# mainboard.net
KiCad netlist of a schematic drawn in EAGLE
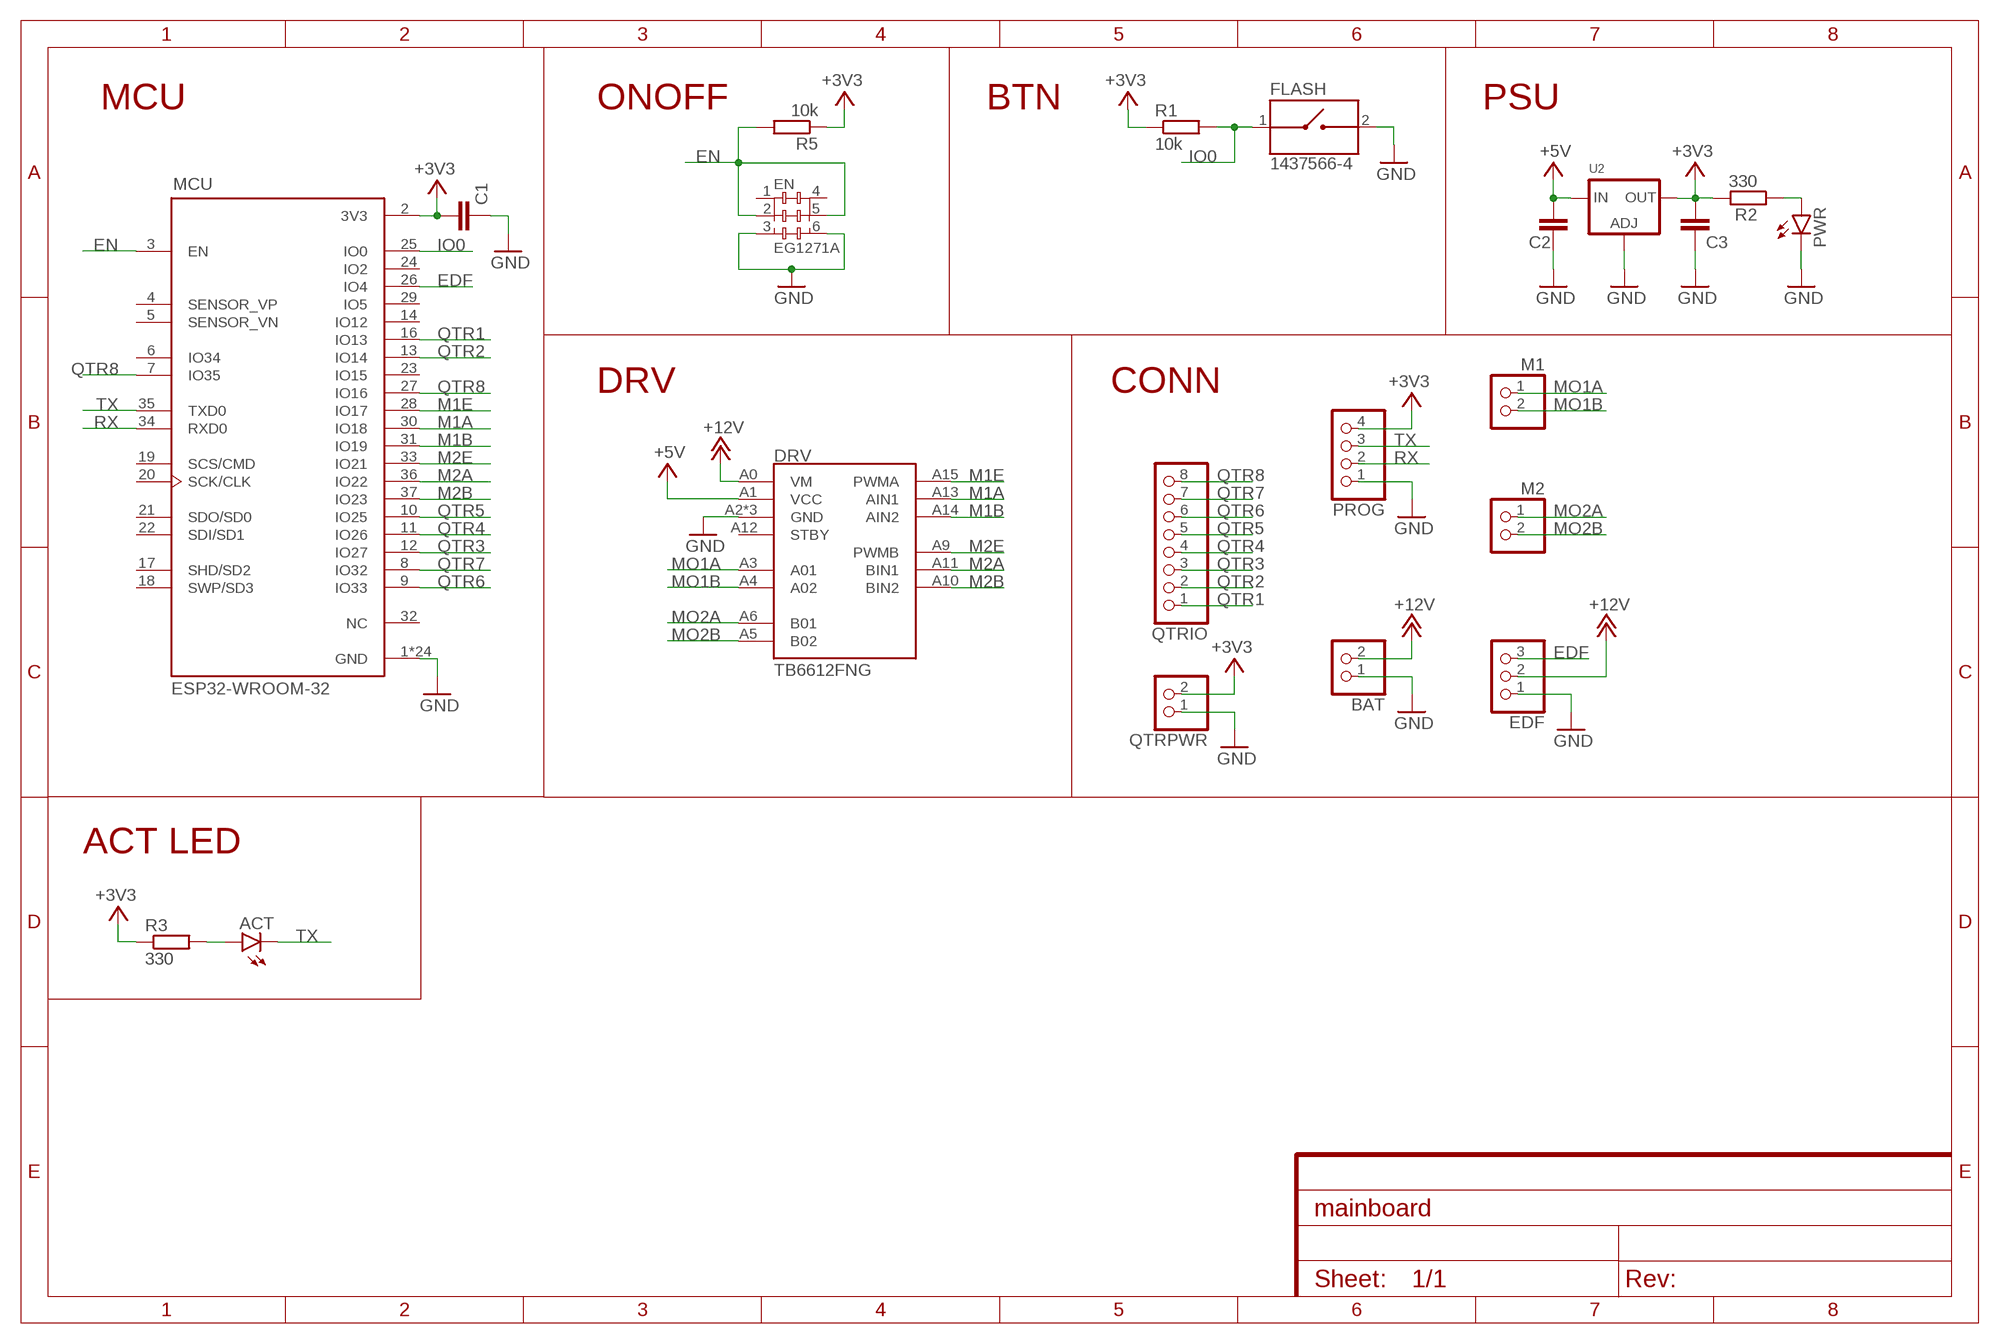
[diagram p0: schematic, sheet 1]

(export (version "E")
  (design (tool "Eeschema 10.0.6"))
  (components
    (comp (ref "ACT")
      (value "LEDCHIPLED_0805")
      (footprint "eagle-import:CHIPLED_0805")
      (libsource (lib "eagle-import") (part "LEDCHIPLED_0805"))
    )
    (comp (ref "BAT")
      (value "PINHD-1X2")
      (footprint "eagle-import:1X02")
      (libsource (lib "eagle-import") (part "PINHD-1X2"))
    )
    (comp (ref "C1")
      (value "C-EUC0805")
      (footprint "eagle-import:C0805")
      (libsource (lib "eagle-import") (part "C-EUC0805"))
    )
    (comp (ref "C2")
      (value "C-EUC0805")
      (footprint "eagle-import:C0805")
      (libsource (lib "eagle-import") (part "C-EUC0805"))
    )
    (comp (ref "C3")
      (value "C-EUC0805")
      (footprint "eagle-import:C0805")
      (libsource (lib "eagle-import") (part "C-EUC0805"))
    )
    (comp (ref "DRV")
      (value "TB6612FNG")
      (footprint "eagle-import:TB6612FNG")
      (libsource (lib "eagle-import") (part "TB6612FNG"))
    )
    (comp (ref "EDF")
      (value "PINHD-1X3")
      (footprint "eagle-import:1X03")
      (libsource (lib "eagle-import") (part "PINHD-1X3"))
    )
    (comp (ref "EN")
      (value "EG1271A")
      (footprint "eagle-import:SW_EG1271A")
      (fields (field (name "MF") "E-Switch"))
      (libsource (lib "eagle-import") (part "EG1271A"))
    )
    (comp (ref "FLASH")
      (value "1437566-4")
      (footprint "eagle-import:SW_1437566-4")
      (fields (field (name "MF") "TE Connectivity"))
      (libsource (lib "eagle-import") (part "1437566-4"))
    )
    (comp (ref "M1")
      (value "PINHD-1X2")
      (footprint "eagle-import:1X02")
      (libsource (lib "eagle-import") (part "PINHD-1X2"))
    )
    (comp (ref "M2")
      (value "PINHD-1X2")
      (footprint "eagle-import:1X02")
      (libsource (lib "eagle-import") (part "PINHD-1X2"))
    )
    (comp (ref "MCU")
      (value "ESP32-WROOM-32")
      (footprint "eagle-import:MODULE_ESP32-WROOM-32")
      (fields (field (name "MF") "Espressif Systems"))
      (libsource (lib "eagle-import") (part "ESP32-WROOM-32"))
    )
    (comp (ref "PROG")
      (value "PINHD-1X4")
      (footprint "eagle-import:1X04")
      (libsource (lib "eagle-import") (part "PINHD-1X4"))
    )
    (comp (ref "PWR")
      (value "LEDCHIPLED_0805")
      (footprint "eagle-import:CHIPLED_0805")
      (libsource (lib "eagle-import") (part "LEDCHIPLED_0805"))
    )
    (comp (ref "QTRIO")
      (value "PINHD-1X8")
      (footprint "eagle-import:1X08")
      (libsource (lib "eagle-import") (part "PINHD-1X8"))
    )
    (comp (ref "QTRPWR")
      (value "PINHD-1X2")
      (footprint "eagle-import:1X02")
      (libsource (lib "eagle-import") (part "PINHD-1X2"))
    )
    (comp (ref "R1")
      (value "10k")
      (footprint "eagle-import:R0603")
      (libsource (lib "eagle-import") (part "R-EU_R0603"))
    )
    (comp (ref "R2")
      (value "330")
      (footprint "eagle-import:R0603")
      (libsource (lib "eagle-import") (part "R-EU_R0603"))
    )
    (comp (ref "R3")
      (value "330")
      (footprint "eagle-import:R0603")
      (libsource (lib "eagle-import") (part "R-EU_R0603"))
    )
    (comp (ref "R5")
      (value "10k")
      (footprint "eagle-import:R0603")
      (libsource (lib "eagle-import") (part "R-EU_R0603"))
    )
    (comp (ref "U2")
      (value "LM1117SOT223-WAVE")
      (footprint "eagle-import:SOT223-W")
      (libsource (lib "eagle-import") (part "LM1117SOT223-WAVE"))
    )
  )
  (nets
    (net (code "1") (name "+3V3") (class "Default")
      (node (ref "C1") (pin "1") (pinfunction "1_1") (pintype "passive"))
      (node (ref "C3") (pin "1") (pinfunction "1_1") (pintype "passive"))
      (node (ref "MCU") (pin "2") (pinfunction "3V3_2") (pintype "power_in"))
      (node (ref "PROG") (pin "4") (pinfunction "4_4") (pintype "passive"))
      (node (ref "QTRPWR") (pin "2") (pinfunction "2_2") (pintype "passive"))
      (node (ref "R1") (pin "1") (pinfunction "1_1") (pintype "passive"))
      (node (ref "R2") (pin "2") (pinfunction "2_2") (pintype "passive"))
      (node (ref "R3") (pin "1") (pinfunction "1_1") (pintype "passive"))
      (node (ref "R5") (pin "1") (pinfunction "1_1") (pintype "passive"))
      (node (ref "U2") (pin "2") (pinfunction "OUT_2") (pintype "passive"))
    )
    (net (code "2") (name "+5V") (class "Default")
      (node (ref "C2") (pin "1") (pinfunction "1_1") (pintype "passive"))
      (node (ref "DRV") (pin "A1") (pinfunction "VCC_A1") (pintype "bidirectional"))
      (node (ref "U2") (pin "3") (pinfunction "IN_3") (pintype "input"))
    )
    (net (code "3") (name "+12V") (class "Default")
      (node (ref "BAT") (pin "2") (pinfunction "2_2") (pintype "passive"))
      (node (ref "DRV") (pin "A0") (pinfunction "VM_A0") (pintype "bidirectional"))
      (node (ref "EDF") (pin "2") (pinfunction "2_2") (pintype "passive"))
    )
    (net (code "4") (name "/EDF") (class "Default")
      (node (ref "EDF") (pin "3") (pinfunction "3_3") (pintype "passive"))
      (node (ref "MCU") (pin "26") (pinfunction "IO4_26") (pintype "bidirectional"))
    )
    (net (code "5") (name "/EN") (class "Default")
      (node (ref "EN") (pin "2") (pinfunction "2_2") (pintype "passive"))
      (node (ref "EN") (pin "5") (pinfunction "5_5") (pintype "passive"))
      (node (ref "MCU") (pin "3") (pinfunction "EN_3") (pintype "input"))
      (node (ref "R5") (pin "2") (pinfunction "2_2") (pintype "passive"))
    )
    (net (code "6") (name "/IO0") (class "Default")
      (node (ref "FLASH") (pin "1") (pinfunction "1_1") (pintype "passive"))
      (node (ref "MCU") (pin "25") (pinfunction "IO0_25") (pintype "bidirectional"))
      (node (ref "R1") (pin "2") (pinfunction "2_2") (pintype "passive"))
    )
    (net (code "7") (name "/M1A") (class "Default")
      (node (ref "DRV") (pin "A13") (pinfunction "AIN1_A13") (pintype "bidirectional"))
      (node (ref "MCU") (pin "30") (pinfunction "IO18_30") (pintype "bidirectional"))
    )
    (net (code "8") (name "/M1B") (class "Default")
      (node (ref "DRV") (pin "A14") (pinfunction "AIN2_A14") (pintype "bidirectional"))
      (node (ref "MCU") (pin "31") (pinfunction "IO19_31") (pintype "bidirectional"))
    )
    (net (code "9") (name "/M1E") (class "Default")
      (node (ref "DRV") (pin "A15") (pinfunction "PWMA_A15") (pintype "bidirectional"))
      (node (ref "MCU") (pin "28") (pinfunction "IO17_28") (pintype "bidirectional"))
    )
    (net (code "10") (name "/M2A") (class "Default")
      (node (ref "DRV") (pin "A11") (pinfunction "BIN1_A11") (pintype "bidirectional"))
      (node (ref "MCU") (pin "36") (pinfunction "IO22_36") (pintype "bidirectional"))
    )
    (net (code "11") (name "/M2B") (class "Default")
      (node (ref "DRV") (pin "A10") (pinfunction "BIN2_A10") (pintype "bidirectional"))
      (node (ref "MCU") (pin "37") (pinfunction "IO23_37") (pintype "bidirectional"))
    )
    (net (code "12") (name "/M2E") (class "Default")
      (node (ref "DRV") (pin "A9") (pinfunction "PWMB_A9") (pintype "bidirectional"))
      (node (ref "MCU") (pin "33") (pinfunction "IO21_33") (pintype "bidirectional"))
    )
    (net (code "13") (name "/MO1A") (class "Default")
      (node (ref "DRV") (pin "A3") (pinfunction "A01_A3") (pintype "bidirectional"))
      (node (ref "M1") (pin "1") (pinfunction "1_1") (pintype "passive"))
    )
    (net (code "14") (name "/MO1B") (class "Default")
      (node (ref "DRV") (pin "A4") (pinfunction "A02_A4") (pintype "bidirectional"))
      (node (ref "M1") (pin "2") (pinfunction "2_2") (pintype "passive"))
    )
    (net (code "15") (name "/MO2A") (class "Default")
      (node (ref "DRV") (pin "A6") (pinfunction "B01_A6") (pintype "bidirectional"))
      (node (ref "M2") (pin "1") (pinfunction "1_1") (pintype "passive"))
    )
    (net (code "16") (name "/MO2B") (class "Default")
      (node (ref "DRV") (pin "A5") (pinfunction "B02_A5") (pintype "bidirectional"))
      (node (ref "M2") (pin "2") (pinfunction "2_2") (pintype "passive"))
    )
    (net (code "17") (name "/QTR1") (class "Default")
      (node (ref "MCU") (pin "16") (pinfunction "IO13_16") (pintype "bidirectional"))
      (node (ref "QTRIO") (pin "1") (pinfunction "1_1") (pintype "passive"))
    )
    (net (code "18") (name "/QTR2") (class "Default")
      (node (ref "MCU") (pin "13") (pinfunction "IO14_13") (pintype "bidirectional"))
      (node (ref "QTRIO") (pin "2") (pinfunction "2_2") (pintype "passive"))
    )
    (net (code "19") (name "/QTR3") (class "Default")
      (node (ref "MCU") (pin "12") (pinfunction "IO27_12") (pintype "bidirectional"))
      (node (ref "QTRIO") (pin "3") (pinfunction "3_3") (pintype "passive"))
    )
    (net (code "20") (name "/QTR4") (class "Default")
      (node (ref "MCU") (pin "11") (pinfunction "IO26_11") (pintype "bidirectional"))
      (node (ref "QTRIO") (pin "4") (pinfunction "4_4") (pintype "passive"))
    )
    (net (code "21") (name "/QTR5") (class "Default")
      (node (ref "MCU") (pin "10") (pinfunction "IO25_10") (pintype "bidirectional"))
      (node (ref "QTRIO") (pin "5") (pinfunction "5_5") (pintype "passive"))
    )
    (net (code "22") (name "/QTR6") (class "Default")
      (node (ref "MCU") (pin "9") (pinfunction "IO33_9") (pintype "bidirectional"))
      (node (ref "QTRIO") (pin "6") (pinfunction "6_6") (pintype "passive"))
    )
    (net (code "23") (name "/QTR7") (class "Default")
      (node (ref "MCU") (pin "8") (pinfunction "IO32_8") (pintype "bidirectional"))
      (node (ref "QTRIO") (pin "7") (pinfunction "7_7") (pintype "passive"))
    )
    (net (code "24") (name "/QTR8") (class "Default")
      (node (ref "MCU") (pin "27") (pinfunction "IO16_27") (pintype "bidirectional"))
      (node (ref "MCU") (pin "7") (pinfunction "IO35_7") (pintype "input"))
      (node (ref "QTRIO") (pin "8") (pinfunction "8_8") (pintype "passive"))
    )
    (net (code "25") (name "/RX") (class "Default")
      (node (ref "MCU") (pin "34") (pinfunction "RXD0_34") (pintype "bidirectional"))
      (node (ref "PROG") (pin "2") (pinfunction "2_2") (pintype "passive"))
    )
    (net (code "26") (name "/TX") (class "Default")
      (node (ref "ACT") (pin "C") (pinfunction "C_C") (pintype "passive"))
      (node (ref "MCU") (pin "35") (pinfunction "TXD0_35") (pintype "bidirectional"))
      (node (ref "PROG") (pin "3") (pinfunction "3_3") (pintype "passive"))
    )
    (net (code "27") (name "GND") (class "Default")
      (node (ref "BAT") (pin "1") (pinfunction "1_1") (pintype "passive"))
      (node (ref "C1") (pin "2") (pinfunction "2_2") (pintype "passive"))
      (node (ref "C2") (pin "2") (pinfunction "2_2") (pintype "passive"))
      (node (ref "C3") (pin "2") (pinfunction "2_2") (pintype "passive"))
      (node (ref "DRV") (pin "A2") (pinfunction "GND_A2") (pintype "bidirectional"))
      (node (ref "DRV") (pin "A7") (pinfunction "GND_A7") (pintype "bidirectional"))
      (node (ref "DRV") (pin "A8") (pinfunction "GND_A8") (pintype "bidirectional"))
      (node (ref "EDF") (pin "1") (pinfunction "1_1") (pintype "passive"))
      (node (ref "EN") (pin "3") (pinfunction "3_3") (pintype "passive"))
      (node (ref "EN") (pin "6") (pinfunction "6_6") (pintype "passive"))
      (node (ref "FLASH") (pin "2") (pinfunction "2_2") (pintype "passive"))
      (node (ref "MCU") (pin "1") (pinfunction "GND_1") (pintype "power_in"))
      (node (ref "MCU") (pin "15") (pinfunction "GND_15") (pintype "power_in"))
      (node (ref "MCU") (pin "38") (pinfunction "GND_38") (pintype "power_in"))
      (node (ref "MCU") (pin "39_1") (pinfunction "GND_39_1") (pintype "power_in"))
      (node (ref "MCU") (pin "39_10") (pinfunction "GND_39_10") (pintype "power_in"))
      (node (ref "MCU") (pin "39_11") (pinfunction "GND_39_11") (pintype "power_in"))
      (node (ref "MCU") (pin "39_12") (pinfunction "GND_39_12") (pintype "power_in"))
      (node (ref "MCU") (pin "39_13") (pinfunction "GND_39_13") (pintype "power_in"))
      (node (ref "MCU") (pin "39_14") (pinfunction "GND_39_14") (pintype "power_in"))
      (node (ref "MCU") (pin "39_15") (pinfunction "GND_39_15") (pintype "power_in"))
      (node (ref "MCU") (pin "39_16") (pinfunction "GND_39_16") (pintype "power_in"))
      (node (ref "MCU") (pin "39_17") (pinfunction "GND_39_17") (pintype "power_in"))
      (node (ref "MCU") (pin "39_18") (pinfunction "GND_39_18") (pintype "power_in"))
      (node (ref "MCU") (pin "39_19") (pinfunction "GND_39_19") (pintype "power_in"))
      (node (ref "MCU") (pin "39_2") (pinfunction "GND_39_2") (pintype "power_in"))
      (node (ref "MCU") (pin "39_20") (pinfunction "GND_39_20") (pintype "power_in"))
      (node (ref "MCU") (pin "39_21") (pinfunction "GND_39_21") (pintype "power_in"))
      (node (ref "MCU") (pin "39_3") (pinfunction "GND_39_3") (pintype "power_in"))
      (node (ref "MCU") (pin "39_4") (pinfunction "GND_39_4") (pintype "power_in"))
      (node (ref "MCU") (pin "39_5") (pinfunction "GND_39_5") (pintype "power_in"))
      (node (ref "MCU") (pin "39_6") (pinfunction "GND_39_6") (pintype "power_in"))
      (node (ref "MCU") (pin "39_7") (pinfunction "GND_39_7") (pintype "power_in"))
      (node (ref "MCU") (pin "39_8") (pinfunction "GND_39_8") (pintype "power_in"))
      (node (ref "MCU") (pin "39_9") (pinfunction "GND_39_9") (pintype "power_in"))
      (node (ref "PROG") (pin "1") (pinfunction "1_1") (pintype "passive"))
      (node (ref "PWR") (pin "C") (pinfunction "C_C") (pintype "passive"))
      (node (ref "QTRPWR") (pin "1") (pinfunction "1_1") (pintype "passive"))
      (node (ref "U2") (pin "1") (pinfunction "ADJ_1") (pintype "input"))
    )
    (net (code "28") (name "Net-(ACT-PadA)") (class "Default")
      (node (ref "ACT") (pin "A") (pinfunction "A_A") (pintype "passive"))
      (node (ref "R3") (pin "2") (pinfunction "2_2") (pintype "passive"))
    )
    (net (code "29") (name "Net-(PWR-PadA)") (class "Default")
      (node (ref "PWR") (pin "A") (pinfunction "A_A") (pintype "passive"))
      (node (ref "R2") (pin "1") (pinfunction "1_1") (pintype "passive"))
    )
    (net (code "30") (name "unconnected-(DRV-STBY-PadA12)") (class "Default")
      (node (ref "DRV") (pin "A12") (pinfunction "STBY_A12") (pintype "bidirectional"))
    )
    (net (code "31") (name "unconnected-(EN-Pad1)") (class "Default")
      (node (ref "EN") (pin "1") (pinfunction "1_1") (pintype "passive"))
    )
    (net (code "32") (name "unconnected-(EN-Pad4)") (class "Default")
      (node (ref "EN") (pin "4") (pinfunction "4_4") (pintype "passive"))
    )
    (net (code "33") (name "unconnected-(MCU-IO2-Pad24)") (class "Default")
      (node (ref "MCU") (pin "24") (pinfunction "IO2_24") (pintype "bidirectional"))
    )
    (net (code "34") (name "unconnected-(MCU-IO5-Pad29)") (class "Default")
      (node (ref "MCU") (pin "29") (pinfunction "IO5_29") (pintype "bidirectional"))
    )
    (net (code "35") (name "unconnected-(MCU-IO12-Pad14)") (class "Default")
      (node (ref "MCU") (pin "14") (pinfunction "IO12_14") (pintype "bidirectional"))
    )
    (net (code "36") (name "unconnected-(MCU-IO15-Pad23)") (class "Default")
      (node (ref "MCU") (pin "23") (pinfunction "IO15_23") (pintype "bidirectional"))
    )
    (net (code "37") (name "unconnected-(MCU-IO34-Pad6)") (class "Default")
      (node (ref "MCU") (pin "6") (pinfunction "IO34_6") (pintype "input"))
    )
    (net (code "38") (name "unconnected-(MCU-NC-Pad32)") (class "Default")
      (node (ref "MCU") (pin "32") (pinfunction "NC_32") (pintype "no_connect"))
    )
    (net (code "39") (name "unconnected-(MCU-SCK{slash}CLK-Pad20)") (class "Default")
      (node (ref "MCU") (pin "20") (pinfunction "SCK/CLK_20") (pintype "bidirectional"))
    )
    (net (code "40") (name "unconnected-(MCU-SCS{slash}CMD-Pad19)") (class "Default")
      (node (ref "MCU") (pin "19") (pinfunction "SCS/CMD_19") (pintype "bidirectional"))
    )
    (net (code "41") (name "unconnected-(MCU-SDI{slash}SD1-Pad22)") (class "Default")
      (node (ref "MCU") (pin "22") (pinfunction "SDI/SD1_22") (pintype "bidirectional"))
    )
    (net (code "42") (name "unconnected-(MCU-SDO{slash}SD0-Pad21)") (class "Default")
      (node (ref "MCU") (pin "21") (pinfunction "SDO/SD0_21") (pintype "bidirectional"))
    )
    (net (code "43") (name "unconnected-(MCU-SENSOR_VN-Pad5)") (class "Default")
      (node (ref "MCU") (pin "5") (pinfunction "SENSOR_VN_5") (pintype "input"))
    )
    (net (code "44") (name "unconnected-(MCU-SENSOR_VP-Pad4)") (class "Default")
      (node (ref "MCU") (pin "4") (pinfunction "SENSOR_VP_4") (pintype "input"))
    )
    (net (code "45") (name "unconnected-(MCU-SHD{slash}SD2-Pad17)") (class "Default")
      (node (ref "MCU") (pin "17") (pinfunction "SHD/SD2_17") (pintype "bidirectional"))
    )
    (net (code "46") (name "unconnected-(MCU-SWP{slash}SD3-Pad18)") (class "Default")
      (node (ref "MCU") (pin "18") (pinfunction "SWP/SD3_18") (pintype "bidirectional"))
    )
  )
)
